# x.net
KiCad netlist of a schematic drawn in Altium Designer
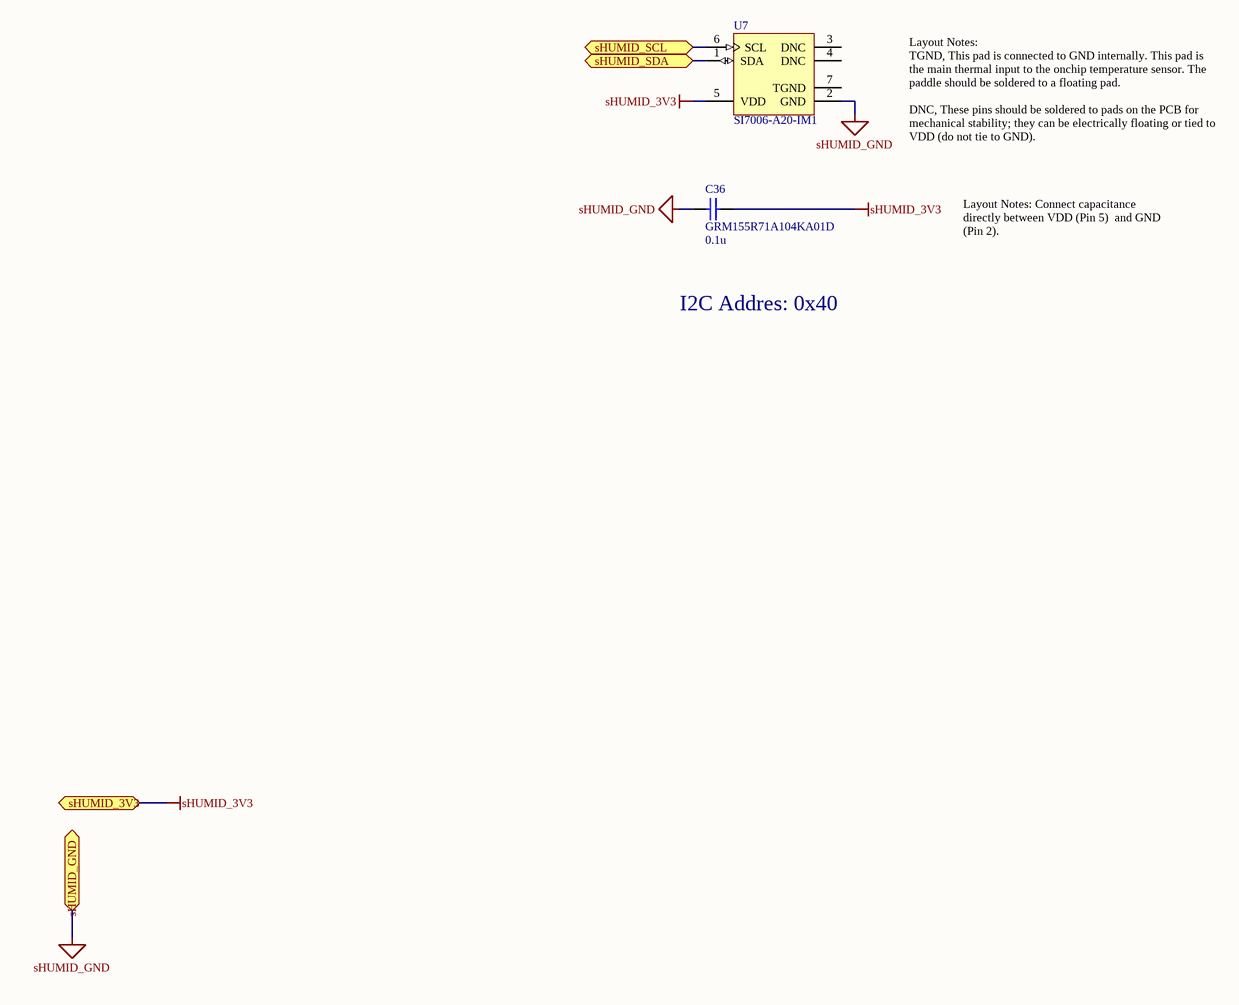
[diagram p0: x.SchDoc]

(export (version "E")
  (design (tool "Eeschema 10.0.6"))
  (components
    (comp (ref "C36")
      (value "GRM155R71A104KA01D")
      (footprint "0402")
      (description "-55-125C, 1005, 10V, X7R, ±10%")
      (fields (field (name "ALTIUM_VALUE") "0.1u"))
      (libsource (lib "standard_capacitors") (part "GRM155R71AxxxKdddd"))
    )
    (comp (ref "U7")
      (value "SI7006-A20-IM1")
      (footprint "SLAB-DFN-6-1500X2400TP_V")
      (description "I2C Humidity and Temperature Sensor, 1.9 to 3.6 V, -40 to 125 degC, 6-Pin DFN, RoHS, Tube")
      (fields (field (name "MANUFACTURER") "Silicon Labs"))
      (libsource (lib "Altium Content Vault") (part "CMP-2000-07060-1"))
    )
  )
  (nets
    (net (code "1") (name "/sHUMID_SCL") (class "Default")
      (node (ref "U7") (pin "6") (pinfunction "SCL_6") (pintype "input"))
    )
    (net (code "2") (name "/sHUMID_SDA") (class "Default")
      (node (ref "U7") (pin "1") (pinfunction "SDA_1") (pintype "bidirectional"))
    )
    (net (code "3") (name "sHUMID_3V3") (class "Default")
      (node (ref "C36") (pin "2") (pinfunction "2_2") (pintype "passive"))
      (node (ref "U7") (pin "5") (pinfunction "VDD_5") (pintype "power_in"))
    )
    (net (code "4") (name "sHUMID_GND") (class "Default")
      (node (ref "C36") (pin "1") (pinfunction "1_1") (pintype "passive"))
      (node (ref "U7") (pin "2") (pinfunction "GND_2") (pintype "power_in"))
    )
    (net (code "5") (name "unconnected-(U7-DNC-Pad3)") (class "Default")
      (node (ref "U7") (pin "3") (pinfunction "DNC_3") (pintype "passive"))
    )
    (net (code "6") (name "unconnected-(U7-DNC-Pad4)") (class "Default")
      (node (ref "U7") (pin "4") (pinfunction "DNC_4") (pintype "passive"))
    )
    (net (code "7") (name "unconnected-(U7-TGND-Pad7)") (class "Default")
      (node (ref "U7") (pin "7") (pinfunction "TGND_7") (pintype "power_in"))
    )
  )
)
